# Power.net
KiCad netlist of a schematic drawn in Altium Designer
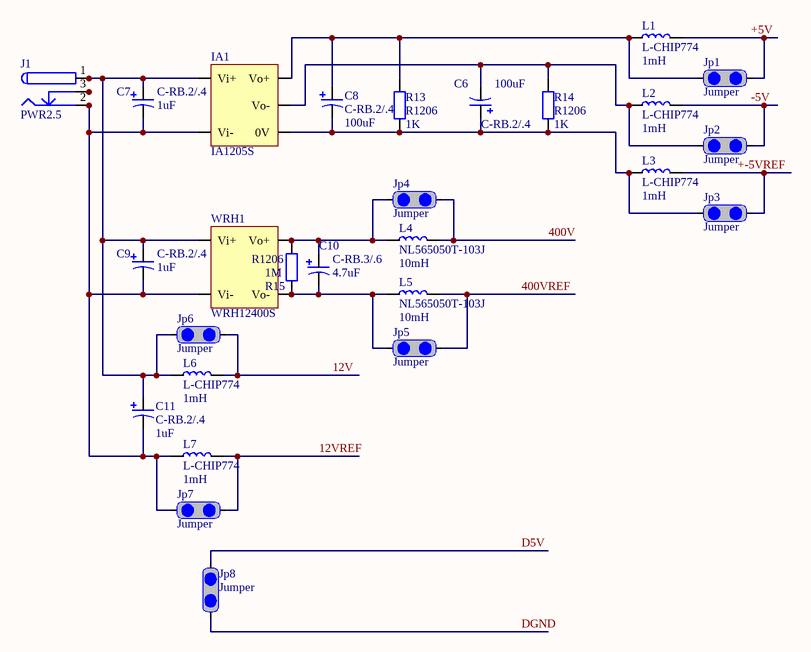
[diagram p0: Power.SchDoc]

(export (version "E")
  (design (tool "Eeschema 10.0.6"))
  (components
    (comp (ref "C6")
      (value "C-RB.2/.4")
      (footprint "RB.2/.4")
      (description "Capacitor")
      (fields (field (name "ALTIUM_VALUE") "100uF"))
      (libsource (lib "UFDLib") (part "C-RB.2/.4"))
    )
    (comp (ref "C7")
      (value "C-RB.2/.4")
      (footprint "RB.2/.4")
      (description "Capacitor")
      (fields (field (name "ALTIUM_VALUE") "1uF"))
      (libsource (lib "UFDLib") (part "C-RB.2/.4"))
    )
    (comp (ref "C8")
      (value "C-RB.2/.4")
      (footprint "RB.2/.4")
      (description "Capacitor")
      (fields (field (name "ALTIUM_VALUE") "100uF"))
      (libsource (lib "UFDLib") (part "C-RB.2/.4"))
    )
    (comp (ref "C9")
      (value "C-RB.2/.4")
      (footprint "RB.2/.4")
      (description "Capacitor")
      (fields (field (name "ALTIUM_VALUE") "1uF"))
      (libsource (lib "UFDLib") (part "C-RB.2/.4"))
    )
    (comp (ref "C10")
      (value "C-RB.3/.6")
      (footprint "RB.3/.6")
      (description "Capacitor")
      (fields (field (name "ALTIUM_VALUE") "4.7uF"))
      (libsource (lib "UFDLib") (part "C-RB.3/.6"))
    )
    (comp (ref "C11")
      (value "C-RB.2/.4")
      (footprint "RB.2/.4")
      (description "Capacitor")
      (fields (field (name "ALTIUM_VALUE") "1uF"))
      (libsource (lib "UFDLib") (part "C-RB.2/.4"))
    )
    (comp (ref "IA1")
      (value "IA1205S")
      (footprint "IA1205S")
      (description "IA1205S,12V to +5V,-5V")
      (libsource (lib "UFDLib") (part "IA1205S"))
    )
    (comp (ref "J1")
      (value "PWR2.5")
      (footprint "KLD-0202")
      (description "Low Voltage Power Supply Connector")
      (fields (field (name "PUBLISHER") "Altium Limited"))
      (libsource (lib "Miscellaneous Connectors") (part "PWR2.5"))
    )
    (comp (ref "Jp1") (value "Jumper") (footprint "JUMPER") (libsource (lib "UFDLib") (part "Jumper")))
    (comp (ref "Jp2") (value "Jumper") (footprint "JUMPER") (libsource (lib "UFDLib") (part "Jumper")))
    (comp (ref "Jp3") (value "Jumper") (footprint "JUMPER") (libsource (lib "UFDLib") (part "Jumper")))
    (comp (ref "Jp4") (value "Jumper") (footprint "JUMPER") (libsource (lib "UFDLib") (part "Jumper")))
    (comp (ref "Jp5") (value "Jumper") (footprint "JUMPER") (libsource (lib "UFDLib") (part "Jumper")))
    (comp (ref "Jp6") (value "Jumper") (footprint "JUMPER") (libsource (lib "UFDLib") (part "Jumper")))
    (comp (ref "Jp7") (value "Jumper") (footprint "JUMPER") (libsource (lib "UFDLib") (part "Jumper")))
    (comp (ref "Jp8") (value "Jumper") (footprint "JUMPER") (libsource (lib "UFDLib") (part "Jumper")))
    (comp (ref "L1")
      (value "L-CHIP774")
      (footprint "INDUCTOR070704")
      (description "Chip Inductor, 7*7*4")
      (fields (field (name "ALTIUM_VALUE") "1mH"))
      (libsource (lib "UFDLib") (part "Inductor070704"))
    )
    (comp (ref "L2")
      (value "L-CHIP774")
      (footprint "INDUCTOR070704")
      (description "Chip Inductor, 7*7*4")
      (fields (field (name "ALTIUM_VALUE") "1mH"))
      (libsource (lib "UFDLib") (part "Inductor070704"))
    )
    (comp (ref "L3")
      (value "L-CHIP774")
      (footprint "INDUCTOR070704")
      (description "Chip Inductor, 7*7*4")
      (fields (field (name "ALTIUM_VALUE") "1mH"))
      (libsource (lib "UFDLib") (part "Inductor070704"))
    )
    (comp (ref "L4")
      (value "NL565050T-103J")
      (footprint "NL565050T")
      (description "NL565050T, 10mH, 150 ohm")
      (fields (field (name "ALTIUM_VALUE") "10mH"))
      (libsource (lib "UFDLib") (part "NL565050T-103J"))
    )
    (comp (ref "L5")
      (value "NL565050T-103J")
      (footprint "NL565050T")
      (description "NL565050T, 10mH, 150 ohm")
      (fields (field (name "ALTIUM_VALUE") "10mH"))
      (libsource (lib "UFDLib") (part "NL565050T-103J"))
    )
    (comp (ref "L6")
      (value "L-CHIP774")
      (footprint "INDUCTOR070704")
      (description "Chip Inductor, 7*7*4")
      (fields (field (name "ALTIUM_VALUE") "1mH"))
      (libsource (lib "UFDLib") (part "Inductor070704"))
    )
    (comp (ref "L7")
      (value "L-CHIP774")
      (footprint "INDUCTOR070704")
      (description "Chip Inductor, 7*7*4")
      (fields (field (name "ALTIUM_VALUE") "1mH"))
      (libsource (lib "UFDLib") (part "Inductor070704"))
    )
    (comp (ref "R13")
      (value "R1206")
      (footprint "1206")
      (description "Resistor, 1206, 1/4W")
      (fields (field (name "ALTIUM_VALUE") "1K"))
      (libsource (lib "UFDLib") (part "R1206"))
    )
    (comp (ref "R14")
      (value "R1206")
      (footprint "1206")
      (description "Resistor, 1206, 1/4W")
      (fields (field (name "ALTIUM_VALUE") "1K"))
      (libsource (lib "UFDLib") (part "R1206"))
    )
    (comp (ref "R15")
      (value "R1206")
      (footprint "1206")
      (description "Resistor, 1206, 1/4W")
      (fields (field (name "ALTIUM_VALUE") "1M"))
      (libsource (lib "UFDLib") (part "R1206"))
    )
    (comp (ref "WRH1")
      (value "WRH12400S")
      (footprint "WRH12400S")
      (description "WRH12400S,12V-400V")
      (libsource (lib "UFDLib") (part "WRH12400S"))
    )
  )
  (nets
    (net (code "1") (name "/+-5VREF") (class "Default")
      (node (ref "Jp3") (pin "2") (pinfunction "b_2") (pintype "passive"))
      (node (ref "L3") (pin "2") (pinfunction "2_2") (pintype "passive"))
    )
    (net (code "2") (name "/+5V") (class "Default")
      (node (ref "Jp1") (pin "2") (pinfunction "b_2") (pintype "passive"))
      (node (ref "L1") (pin "2") (pinfunction "2_2") (pintype "passive"))
    )
    (net (code "3") (name "/-5V") (class "Default")
      (node (ref "Jp2") (pin "2") (pinfunction "b_2") (pintype "passive"))
      (node (ref "L2") (pin "2") (pinfunction "2_2") (pintype "passive"))
    )
    (net (code "4") (name "/12V") (class "Default")
      (node (ref "Jp6") (pin "2") (pinfunction "b_2") (pintype "passive"))
      (node (ref "L6") (pin "2") (pinfunction "2_2") (pintype "passive"))
    )
    (net (code "5") (name "/12VREF") (class "Default")
      (node (ref "Jp7") (pin "2") (pinfunction "b_2") (pintype "passive"))
      (node (ref "L7") (pin "2") (pinfunction "2_2") (pintype "passive"))
    )
    (net (code "6") (name "/400V") (class "Default")
      (node (ref "Jp4") (pin "2") (pinfunction "b_2") (pintype "passive"))
      (node (ref "L4") (pin "2") (pinfunction "2_2") (pintype "passive"))
    )
    (net (code "7") (name "/400VREF") (class "Default")
      (node (ref "Jp5") (pin "2") (pinfunction "b_2") (pintype "passive"))
      (node (ref "L5") (pin "2") (pinfunction "2_2") (pintype "passive"))
    )
    (net (code "8") (name "/D5V") (class "Default")
      (node (ref "Jp8") (pin "2") (pinfunction "b_2") (pintype "passive"))
    )
    (net (code "9") (name "/DGND") (class "Default")
      (node (ref "Jp8") (pin "1") (pinfunction "a_1") (pintype "passive"))
    )
    (net (code "10") (name "Net-(C6-a)") (class "Default")
      (node (ref "C6") (pin "1") (pinfunction "a_1") (pintype "passive"))
      (node (ref "IA1") (pin "9") (pinfunction "Vo-_9") (pintype "passive"))
      (node (ref "Jp2") (pin "1") (pinfunction "a_1") (pintype "passive"))
      (node (ref "L2") (pin "1") (pinfunction "1_1") (pintype "passive"))
      (node (ref "R14") (pin "2") (pinfunction "b_2") (pintype "passive"))
    )
    (net (code "11") (name "Net-(C6-b)") (class "Default")
      (node (ref "C6") (pin "2") (pinfunction "b_2") (pintype "passive"))
      (node (ref "C8") (pin "1") (pinfunction "a_1") (pintype "passive"))
      (node (ref "IA1") (pin "10") (pinfunction "0V_10") (pintype "passive"))
      (node (ref "Jp3") (pin "1") (pinfunction "a_1") (pintype "passive"))
      (node (ref "L3") (pin "1") (pinfunction "1_1") (pintype "passive"))
      (node (ref "R13") (pin "1") (pinfunction "a_1") (pintype "passive"))
      (node (ref "R14") (pin "1") (pinfunction "a_1") (pintype "passive"))
    )
    (net (code "12") (name "Net-(C8-b)") (class "Default")
      (node (ref "C8") (pin "2") (pinfunction "b_2") (pintype "passive"))
      (node (ref "IA1") (pin "7") (pinfunction "Vo+_7") (pintype "passive"))
      (node (ref "Jp1") (pin "1") (pinfunction "a_1") (pintype "passive"))
      (node (ref "L1") (pin "1") (pinfunction "1_1") (pintype "passive"))
      (node (ref "R13") (pin "2") (pinfunction "b_2") (pintype "passive"))
    )
    (net (code "13") (name "Net-(C10-a)") (class "Default")
      (node (ref "C10") (pin "1") (pinfunction "a_1") (pintype "passive"))
      (node (ref "Jp5") (pin "1") (pinfunction "a_1") (pintype "passive"))
      (node (ref "L5") (pin "1") (pinfunction "1_1") (pintype "passive"))
      (node (ref "R15") (pin "1") (pinfunction "a_1") (pintype "passive"))
      (node (ref "WRH1") (pin "5") (pinfunction "Vo-_5") (pintype "passive"))
    )
    (net (code "14") (name "Net-(C10-b)") (class "Default")
      (node (ref "C10") (pin "2") (pinfunction "b_2") (pintype "passive"))
      (node (ref "Jp4") (pin "1") (pinfunction "a_1") (pintype "passive"))
      (node (ref "L4") (pin "1") (pinfunction "1_1") (pintype "passive"))
      (node (ref "R15") (pin "2") (pinfunction "b_2") (pintype "passive"))
      (node (ref "WRH1") (pin "3") (pinfunction "Vo+_3") (pintype "passive"))
    )
    (net (code "15") (name "Net-(C11-a)") (class "Default")
      (node (ref "C11") (pin "1") (pinfunction "a_1") (pintype "passive"))
      (node (ref "C7") (pin "1") (pinfunction "a_1") (pintype "passive"))
      (node (ref "C9") (pin "1") (pinfunction "a_1") (pintype "passive"))
      (node (ref "IA1") (pin "2") (pinfunction "Vi-_2") (pintype "passive"))
      (node (ref "J1") (pin "2") (pinfunction "2_2") (pintype "power_in"))
      (node (ref "J1") (pin "2A") (pinfunction "2A_2A") (pintype "power_in"))
      (node (ref "J1") (pin "2B") (pinfunction "2B_2B") (pintype "power_in"))
      (node (ref "Jp7") (pin "1") (pinfunction "a_1") (pintype "passive"))
      (node (ref "L7") (pin "1") (pinfunction "1_1") (pintype "passive"))
      (node (ref "WRH1") (pin "2") (pinfunction "Vi-_2") (pintype "passive"))
    )
    (net (code "16") (name "Net-(C11-b)") (class "Default")
      (node (ref "C11") (pin "2") (pinfunction "b_2") (pintype "passive"))
      (node (ref "C7") (pin "2") (pinfunction "b_2") (pintype "passive"))
      (node (ref "C9") (pin "2") (pinfunction "b_2") (pintype "passive"))
      (node (ref "IA1") (pin "1") (pinfunction "Vi+_1") (pintype "passive"))
      (node (ref "J1") (pin "1") (pinfunction "1_1") (pintype "power_in"))
      (node (ref "J1") (pin "1A") (pinfunction "1A_1A") (pintype "power_in"))
      (node (ref "J1") (pin "1B") (pinfunction "1B_1B") (pintype "power_in"))
      (node (ref "Jp6") (pin "1") (pinfunction "a_1") (pintype "passive"))
      (node (ref "L6") (pin "1") (pinfunction "1_1") (pintype "passive"))
      (node (ref "WRH1") (pin "1") (pinfunction "Vi+_1") (pintype "passive"))
    )
    (net (code "17") (name "Net-(J1-Pad3)") (class "Default")
      (node (ref "J1") (pin "3") (pinfunction "3_3") (pintype "power_in"))
      (node (ref "J1") (pin "3A") (pinfunction "3A_3A") (pintype "power_in"))
      (node (ref "J1") (pin "3B") (pinfunction "3B_3B") (pintype "power_in"))
    )
  )
)
